# janus.net
KiCad netlist of a schematic drawn in EAGLE
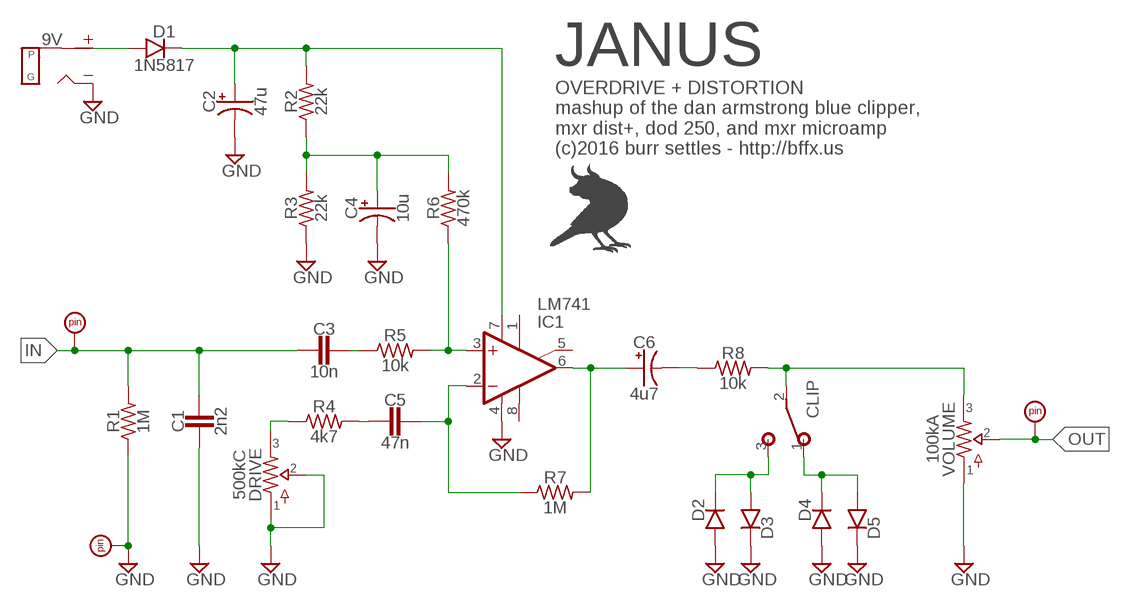
[diagram p0: schematic, sheet 1]

(export (version "E")
  (design (tool "Eeschema 10.0.6"))
  (components
    (comp (ref "9V")
      (value "DC_MONO")
      (footprint "eagle-import:DC")
      (libsource (lib "eagle-import") (part "DC_MONO"))
    )
    (comp (ref "C1")
      (value "2n2")
      (footprint "eagle-import:050X030_025_2")
      (libsource (lib "eagle-import") (part "CER/FILM2"))
    )
    (comp (ref "C2")
      (value "47u")
      (footprint "eagle-import:050_020_1")
      (libsource (lib "eagle-import") (part "0501"))
    )
    (comp (ref "C3")
      (value "10n")
      (footprint "eagle-import:050X030_025_2")
      (libsource (lib "eagle-import") (part "CER/FILM2"))
    )
    (comp (ref "C4")
      (value "10u")
      (footprint "eagle-import:050_020_1")
      (libsource (lib "eagle-import") (part "0501"))
    )
    (comp (ref "C5")
      (value "47n")
      (footprint "eagle-import:050X030_025_2")
      (libsource (lib "eagle-import") (part "CER/FILM2"))
    )
    (comp (ref "C6")
      (value "4u7")
      (footprint "eagle-import:050_020_1")
      (libsource (lib "eagle-import") (part "0501"))
    )
    (comp (ref "CLIP")
      (value "SPDTPADS")
      (footprint "eagle-import:SPDT")
      (libsource (lib "eagle-import") (part "SPDTPADS"))
    )
    (comp (ref "D1")
      (value "1N5817")
      (footprint "eagle-import:DO41-3")
      (libsource (lib "eagle-import") (part "DO41.3"))
    )
    (comp (ref "D2")
      (value "DO35.2")
      (footprint "eagle-import:DO35-2")
      (libsource (lib "eagle-import") (part "DO35.2"))
    )
    (comp (ref "D3")
      (value "DO35.2")
      (footprint "eagle-import:DO35-2")
      (libsource (lib "eagle-import") (part "DO35.2"))
    )
    (comp (ref "D4")
      (value "DO35.3")
      (footprint "eagle-import:DO35-3")
      (libsource (lib "eagle-import") (part "DO35.3"))
    )
    (comp (ref "D5")
      (value "DO35.3")
      (footprint "eagle-import:DO35-3")
      (libsource (lib "eagle-import") (part "DO35.3"))
    )
    (comp (ref "DRIVE")
      (value "500kC")
      (footprint "eagle-import:PADS_SMALL")
      (libsource (lib "eagle-import") (part "POTSSMALL_PADS"))
    )
    (comp (ref "GND")
      (value "PADRND")
      (footprint "eagle-import:ROUND")
      (libsource (lib "eagle-import") (part "PADRND"))
    )
    (comp (ref "IC1")
      (value "LM741")
      (footprint "eagle-import:DIL08")
      (libsource (lib "eagle-import") (part "SINGLETH"))
    )
    (comp (ref "IN")
      (value "PADSQR")
      (footprint "eagle-import:SQUARE")
      (libsource (lib "eagle-import") (part "PADSQR"))
    )
    (comp (ref "OUT")
      (value "PADSQR")
      (footprint "eagle-import:SQUARE")
      (libsource (lib "eagle-import") (part "PADSQR"))
    )
    (comp (ref "R1")
      (value "1M")
      (footprint "eagle-import:R0207_3")
      (libsource (lib "eagle-import") (part "R_.3B"))
    )
    (comp (ref "R2")
      (value "22k")
      (footprint "eagle-import:R0207_3")
      (libsource (lib "eagle-import") (part "R_.3B"))
    )
    (comp (ref "R3")
      (value "22k")
      (footprint "eagle-import:R0207_3")
      (libsource (lib "eagle-import") (part "R_.3B"))
    )
    (comp (ref "R4")
      (value "4k7")
      (footprint "eagle-import:R0207_3")
      (libsource (lib "eagle-import") (part "R_.3B"))
    )
    (comp (ref "R5")
      (value "10k")
      (footprint "eagle-import:R0207_3")
      (libsource (lib "eagle-import") (part "R_.3B"))
    )
    (comp (ref "R6")
      (value "470k")
      (footprint "eagle-import:R0207_3")
      (libsource (lib "eagle-import") (part "R_.3B"))
    )
    (comp (ref "R7")
      (value "1M")
      (footprint "eagle-import:R0207_3")
      (libsource (lib "eagle-import") (part "R_.3B"))
    )
    (comp (ref "R8")
      (value "10k")
      (footprint "eagle-import:R0207_3")
      (libsource (lib "eagle-import") (part "R_.3B"))
    )
    (comp (ref "VOLUME")
      (value "100kA")
      (footprint "eagle-import:PADS_SMALL")
      (libsource (lib "eagle-import") (part "POTSSMALL_PADS"))
    )
  )
  (nets
    (net (code "1") (name "GND") (class "Default")
      (node (ref "9V") (pin "S") (pinfunction "SLEEVE_S") (pintype "passive"))
      (node (ref "C1") (pin "1") (pinfunction "1_1") (pintype "passive"))
      (node (ref "C2") (pin "-") (pinfunction "-_-") (pintype "passive"))
      (node (ref "C4") (pin "-") (pinfunction "-_-") (pintype "passive"))
      (node (ref "D2") (pin "A") (pinfunction "A_A") (pintype "passive"))
      (node (ref "D3") (pin "C") (pinfunction "C_C") (pintype "passive"))
      (node (ref "D4") (pin "A") (pinfunction "A_A") (pintype "passive"))
      (node (ref "D5") (pin "C") (pinfunction "C_C") (pintype "passive"))
      (node (ref "DRIVE") (pin "1") (pinfunction "1_1") (pintype "passive"))
      (node (ref "DRIVE") (pin "2") (pinfunction "2_2") (pintype "passive"))
      (node (ref "GND") (pin "1") (pinfunction "P$1_1") (pintype "bidirectional"))
      (node (ref "IC1") (pin "4") (pinfunction "V-_4") (pintype "power_in"))
      (node (ref "R1") (pin "1") (pinfunction "1_1") (pintype "passive"))
      (node (ref "R3") (pin "1") (pinfunction "1_1") (pintype "passive"))
      (node (ref "VOLUME") (pin "1") (pinfunction "1_1") (pintype "passive"))
    )
    (net (code "2") (name "IN") (class "Default")
      (node (ref "C1") (pin "2") (pinfunction "2_2") (pintype "passive"))
      (node (ref "C3") (pin "2") (pinfunction "2_2") (pintype "passive"))
      (node (ref "IN") (pin "1") (pinfunction "P$1_1") (pintype "bidirectional"))
      (node (ref "R1") (pin "2") (pinfunction "2_2") (pintype "passive"))
    )
    (net (code "3") (name "Net-(9V-TIP)") (class "Default")
      (node (ref "9V") (pin "T") (pinfunction "TIP_T") (pintype "passive"))
      (node (ref "D1") (pin "A") (pinfunction "A_A") (pintype "passive"))
    )
    (net (code "4") (name "Net-(C3-Pad1)") (class "Default")
      (node (ref "C3") (pin "1") (pinfunction "1_1") (pintype "passive"))
      (node (ref "R5") (pin "1") (pinfunction "1_1") (pintype "passive"))
    )
    (net (code "5") (name "Net-(C4-Pad+)") (class "Default")
      (node (ref "C4") (pin "+") (pinfunction "+_+") (pintype "passive"))
      (node (ref "R2") (pin "1") (pinfunction "1_1") (pintype "passive"))
      (node (ref "R3") (pin "2") (pinfunction "2_2") (pintype "passive"))
      (node (ref "R6") (pin "2") (pinfunction "2_2") (pintype "passive"))
    )
    (net (code "6") (name "Net-(C5-Pad2)") (class "Default")
      (node (ref "C5") (pin "2") (pinfunction "2_2") (pintype "passive"))
      (node (ref "R4") (pin "2") (pinfunction "2_2") (pintype "passive"))
    )
    (net (code "7") (name "Net-(C6-Pad-)") (class "Default")
      (node (ref "C6") (pin "-") (pinfunction "-_-") (pintype "passive"))
      (node (ref "R8") (pin "1") (pinfunction "1_1") (pintype "passive"))
    )
    (net (code "8") (name "Net-(CLIP-O)") (class "Default")
      (node (ref "CLIP") (pin "1") (pinfunction "O_1") (pintype "passive"))
      (node (ref "D4") (pin "C") (pinfunction "C_C") (pintype "passive"))
      (node (ref "D5") (pin "A") (pinfunction "A_A") (pintype "passive"))
    )
    (net (code "9") (name "Net-(CLIP-P)") (class "Default")
      (node (ref "CLIP") (pin "2") (pinfunction "P_2") (pintype "passive"))
      (node (ref "R8") (pin "2") (pinfunction "2_2") (pintype "passive"))
      (node (ref "VOLUME") (pin "3") (pinfunction "3_3") (pintype "passive"))
    )
    (net (code "10") (name "Net-(CLIP-S)") (class "Default")
      (node (ref "CLIP") (pin "3") (pinfunction "S_3") (pintype "passive"))
      (node (ref "D2") (pin "C") (pinfunction "C_C") (pintype "passive"))
      (node (ref "D3") (pin "A") (pinfunction "A_A") (pintype "passive"))
    )
    (net (code "11") (name "Net-(DRIVE-Pad3)") (class "Default")
      (node (ref "DRIVE") (pin "3") (pinfunction "3_3") (pintype "passive"))
      (node (ref "R4") (pin "1") (pinfunction "1_1") (pintype "passive"))
    )
    (net (code "12") (name "Net-(IC1-+IN)") (class "Default")
      (node (ref "IC1") (pin "3") (pinfunction "+IN_3") (pintype "input"))
      (node (ref "R5") (pin "2") (pinfunction "2_2") (pintype "passive"))
      (node (ref "R6") (pin "1") (pinfunction "1_1") (pintype "passive"))
    )
    (net (code "13") (name "Net-(IC1--IN)") (class "Default")
      (node (ref "C5") (pin "1") (pinfunction "1_1") (pintype "passive"))
      (node (ref "IC1") (pin "2") (pinfunction "-IN_2") (pintype "input"))
      (node (ref "R7") (pin "1") (pinfunction "1_1") (pintype "passive"))
    )
    (net (code "14") (name "Net-(IC1-OUT)") (class "Default")
      (node (ref "C6") (pin "+") (pinfunction "+_+") (pintype "passive"))
      (node (ref "IC1") (pin "6") (pinfunction "OUT_6") (pintype "output"))
      (node (ref "R7") (pin "2") (pinfunction "2_2") (pintype "passive"))
    )
    (net (code "15") (name "Net-(IC1-V+)") (class "Default")
      (node (ref "C2") (pin "+") (pinfunction "+_+") (pintype "passive"))
      (node (ref "D1") (pin "C") (pinfunction "C_C") (pintype "passive"))
      (node (ref "IC1") (pin "7") (pinfunction "V+_7") (pintype "power_in"))
      (node (ref "R2") (pin "2") (pinfunction "2_2") (pintype "passive"))
    )
    (net (code "16") (name "OUT") (class "Default")
      (node (ref "OUT") (pin "1") (pinfunction "P$1_1") (pintype "bidirectional"))
      (node (ref "VOLUME") (pin "2") (pinfunction "2_2") (pintype "passive"))
    )
    (net (code "17") (name "unconnected-(IC1-ON1-Pad1)") (class "Default")
      (node (ref "IC1") (pin "1") (pinfunction "ON1_1") (pintype "passive"))
    )
    (net (code "18") (name "unconnected-(IC1-ON2-Pad5)") (class "Default")
      (node (ref "IC1") (pin "5") (pinfunction "ON2_5") (pintype "passive"))
    )
    (net (code "19") (name "unconnected-(IC1-OPT-Pad8)") (class "Default")
      (node (ref "IC1") (pin "8") (pinfunction "OPT_8") (pintype "passive"))
    )
  )
)
